# p2_half_bridge.net
KiCad netlist of a schematic drawn in Altium Designer
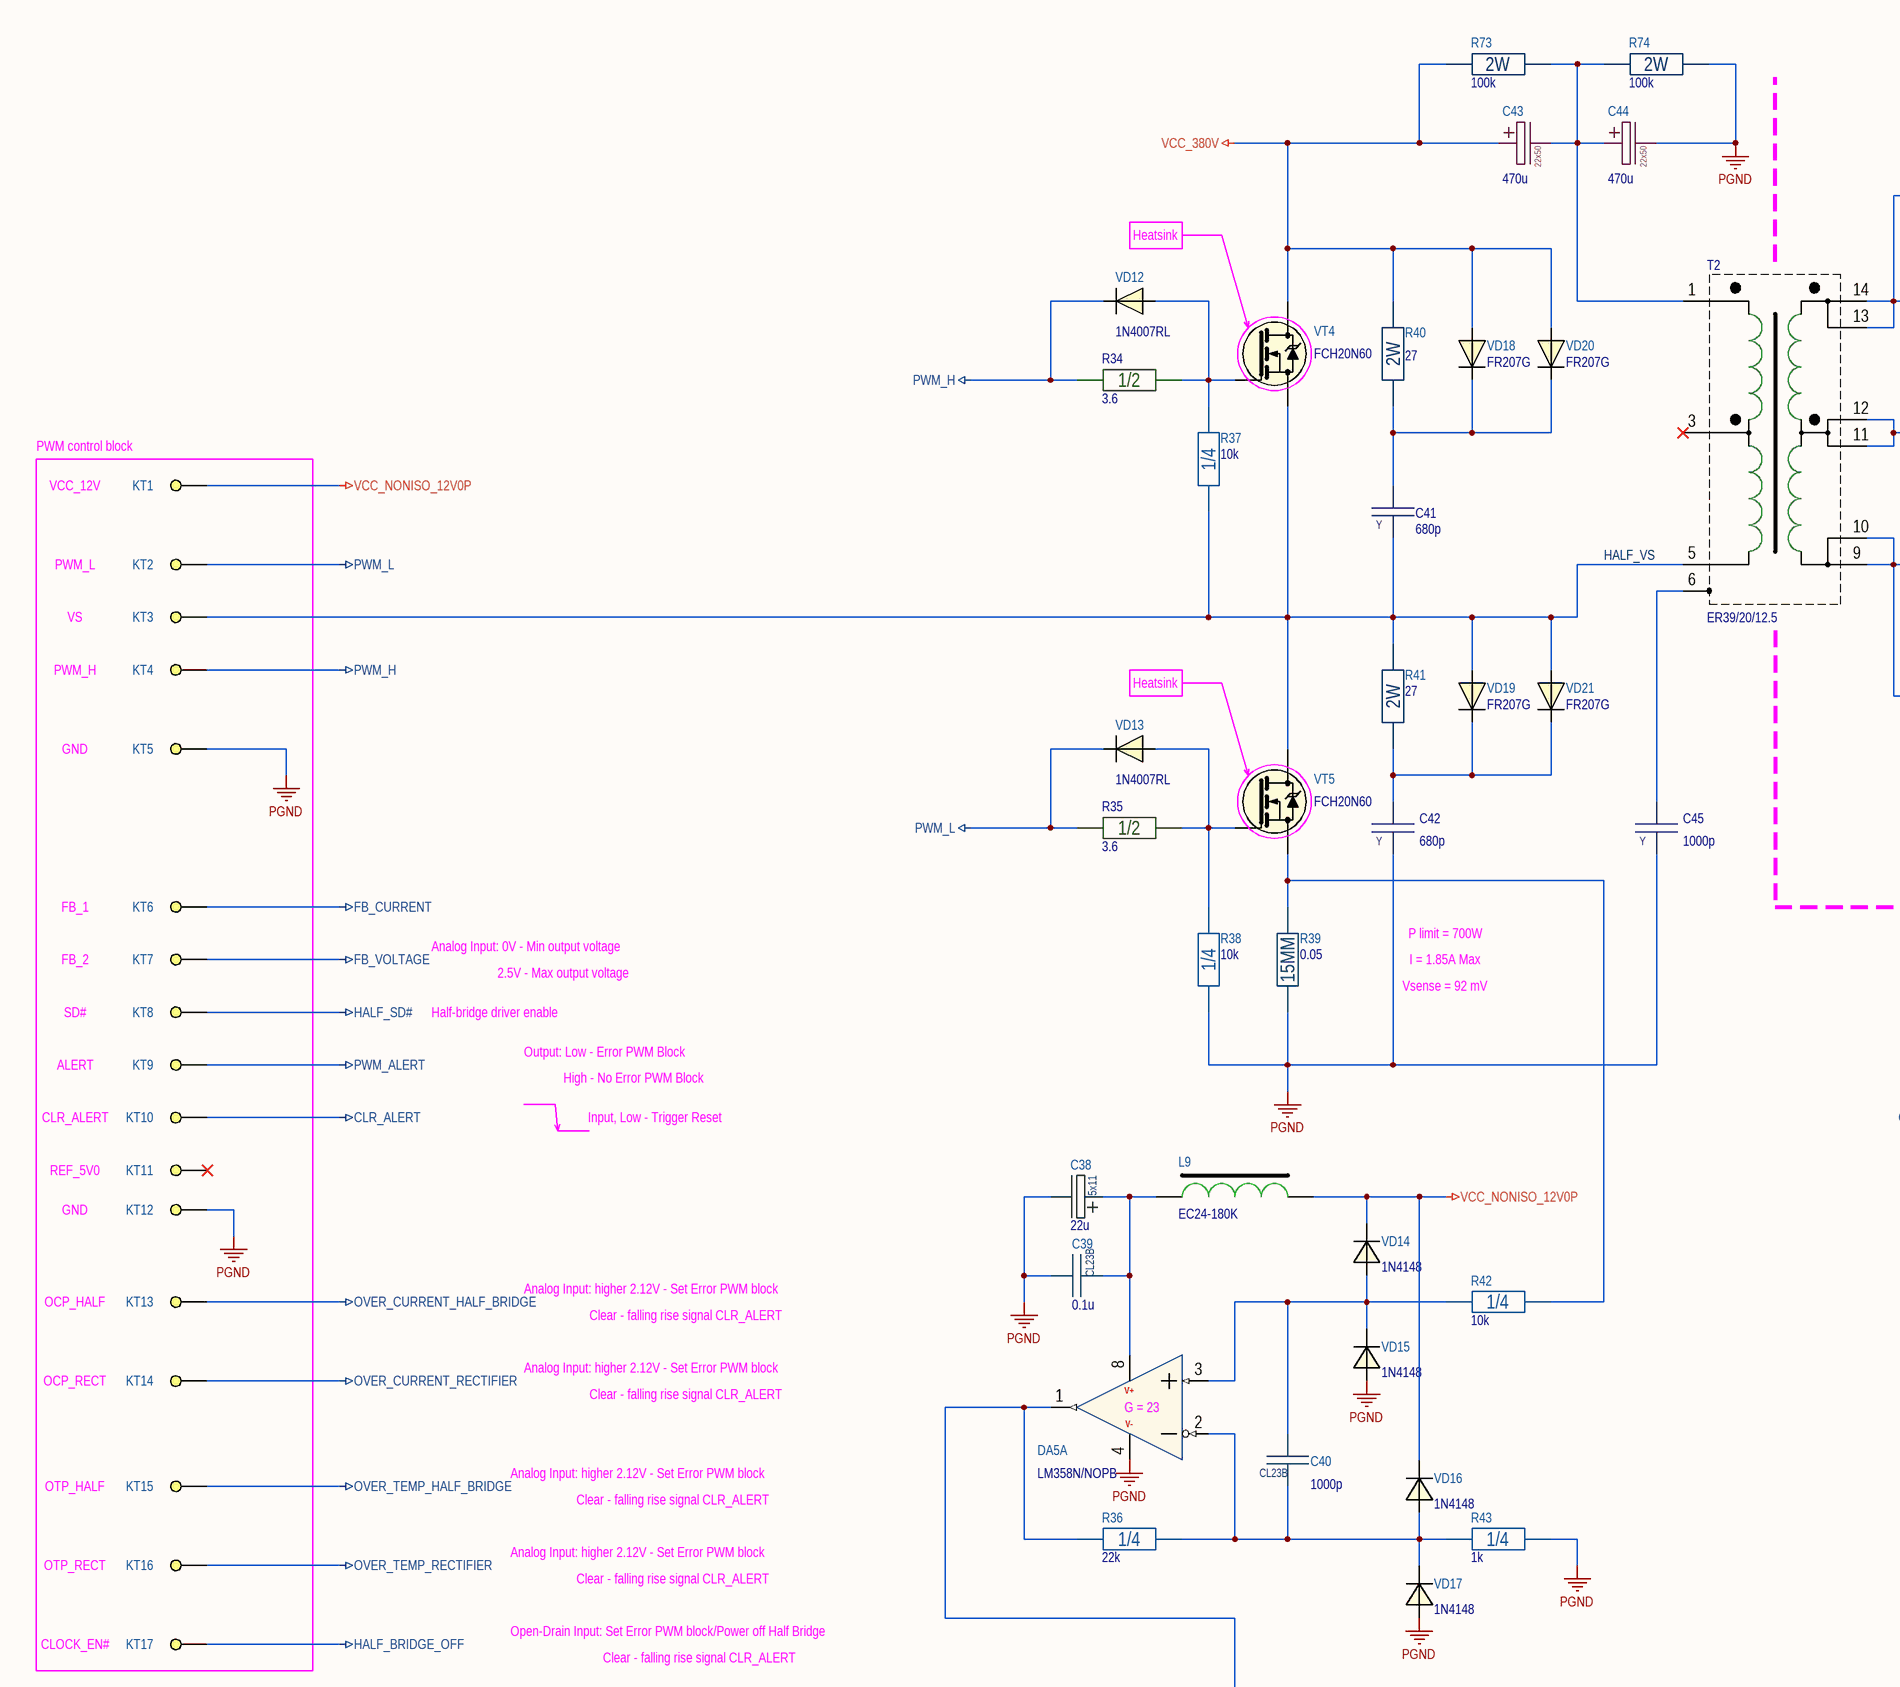
[diagram p0: p2_half_bridge.SchDoc, top left]
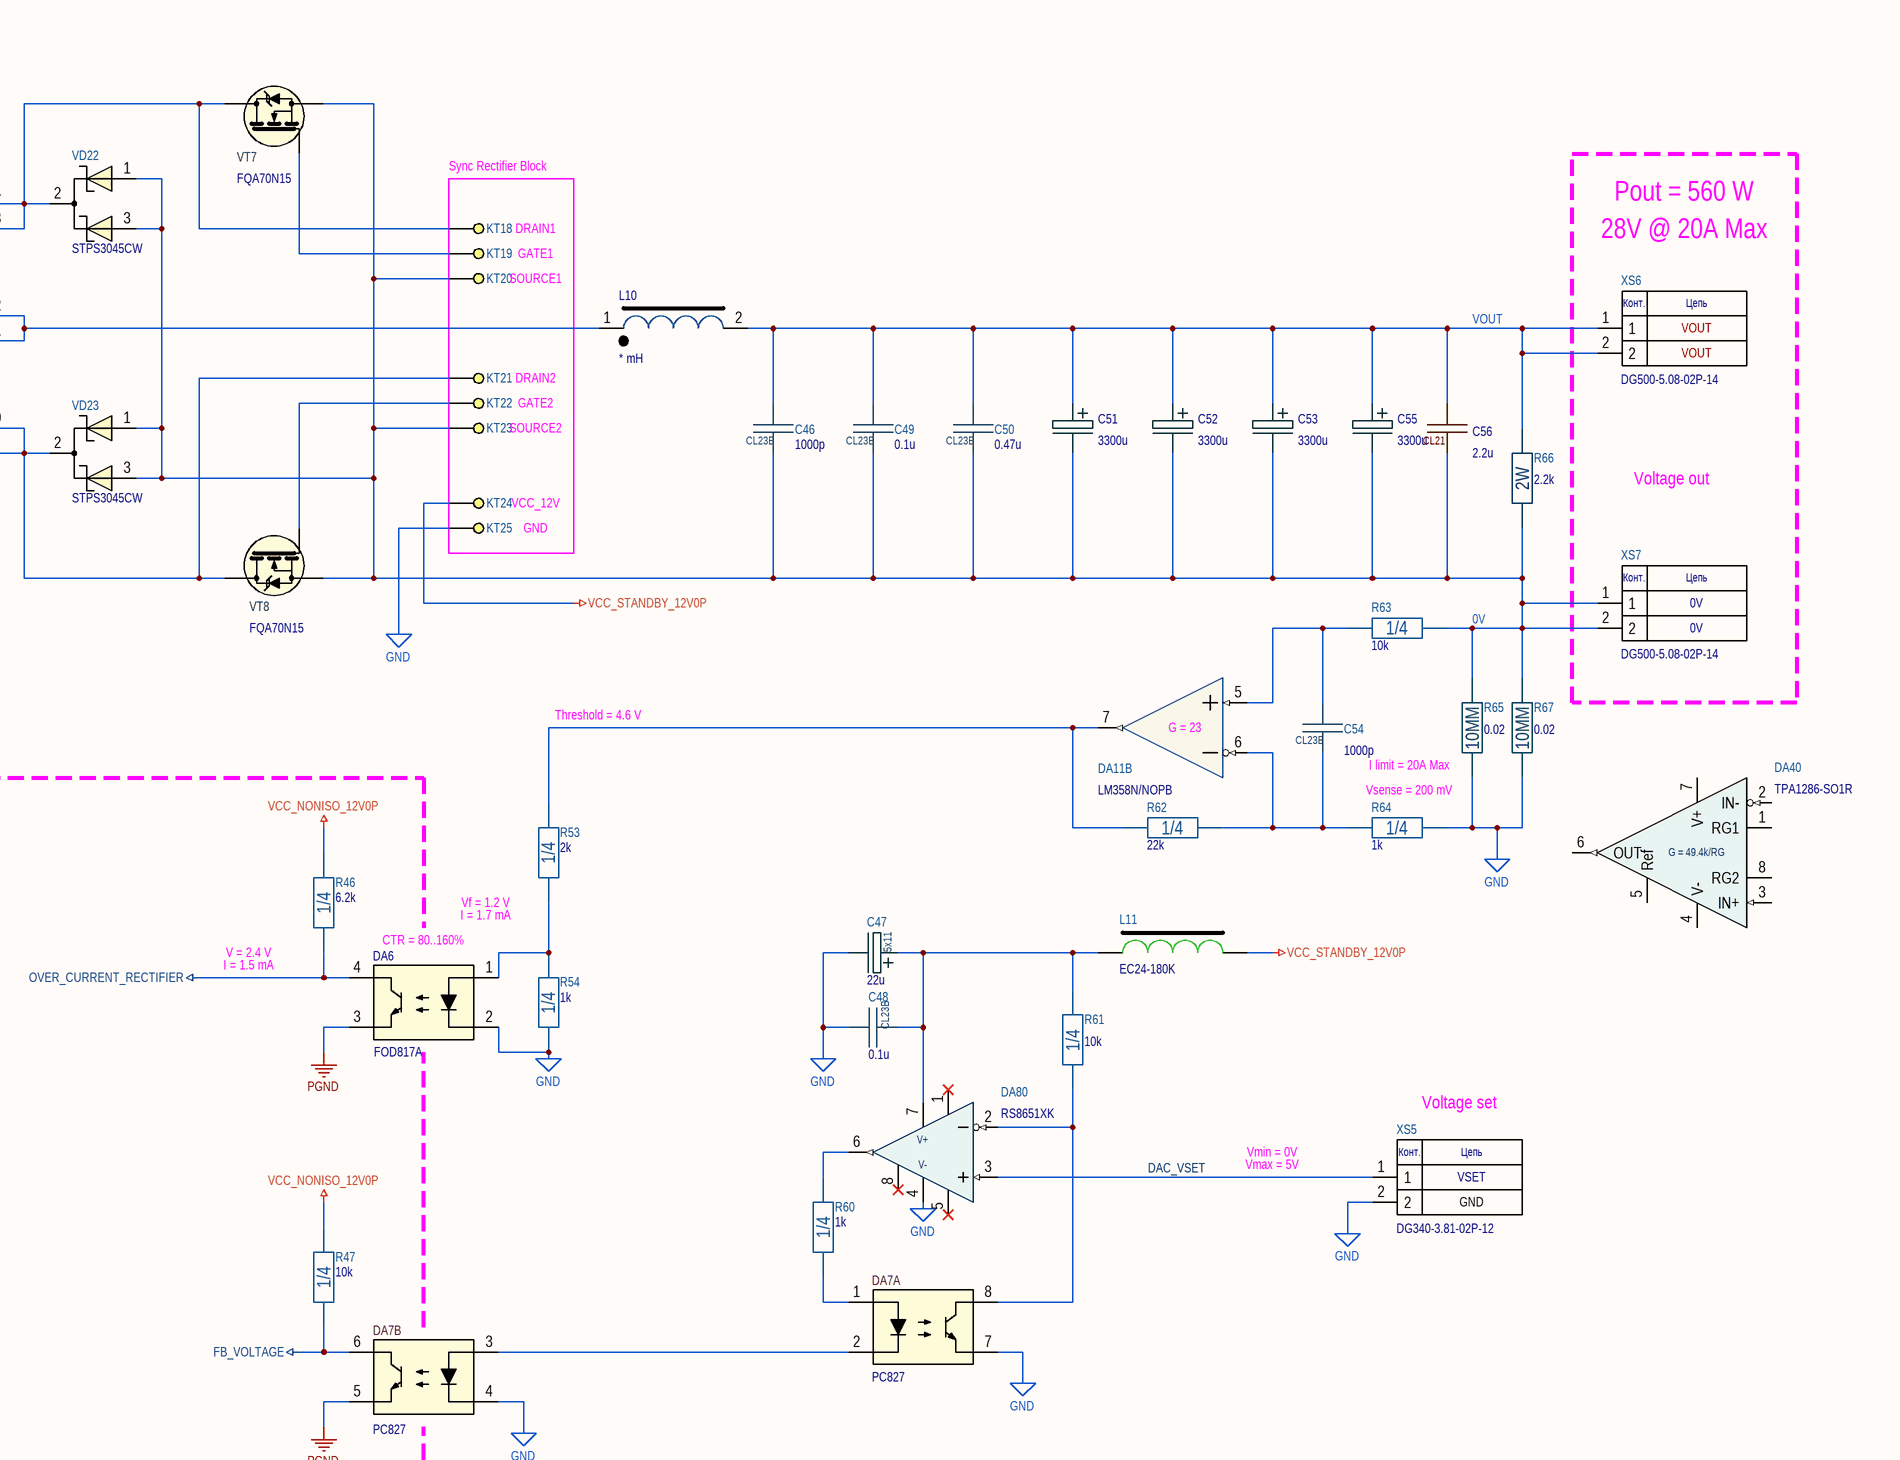
[diagram p1: p2_half_bridge.SchDoc, top right]
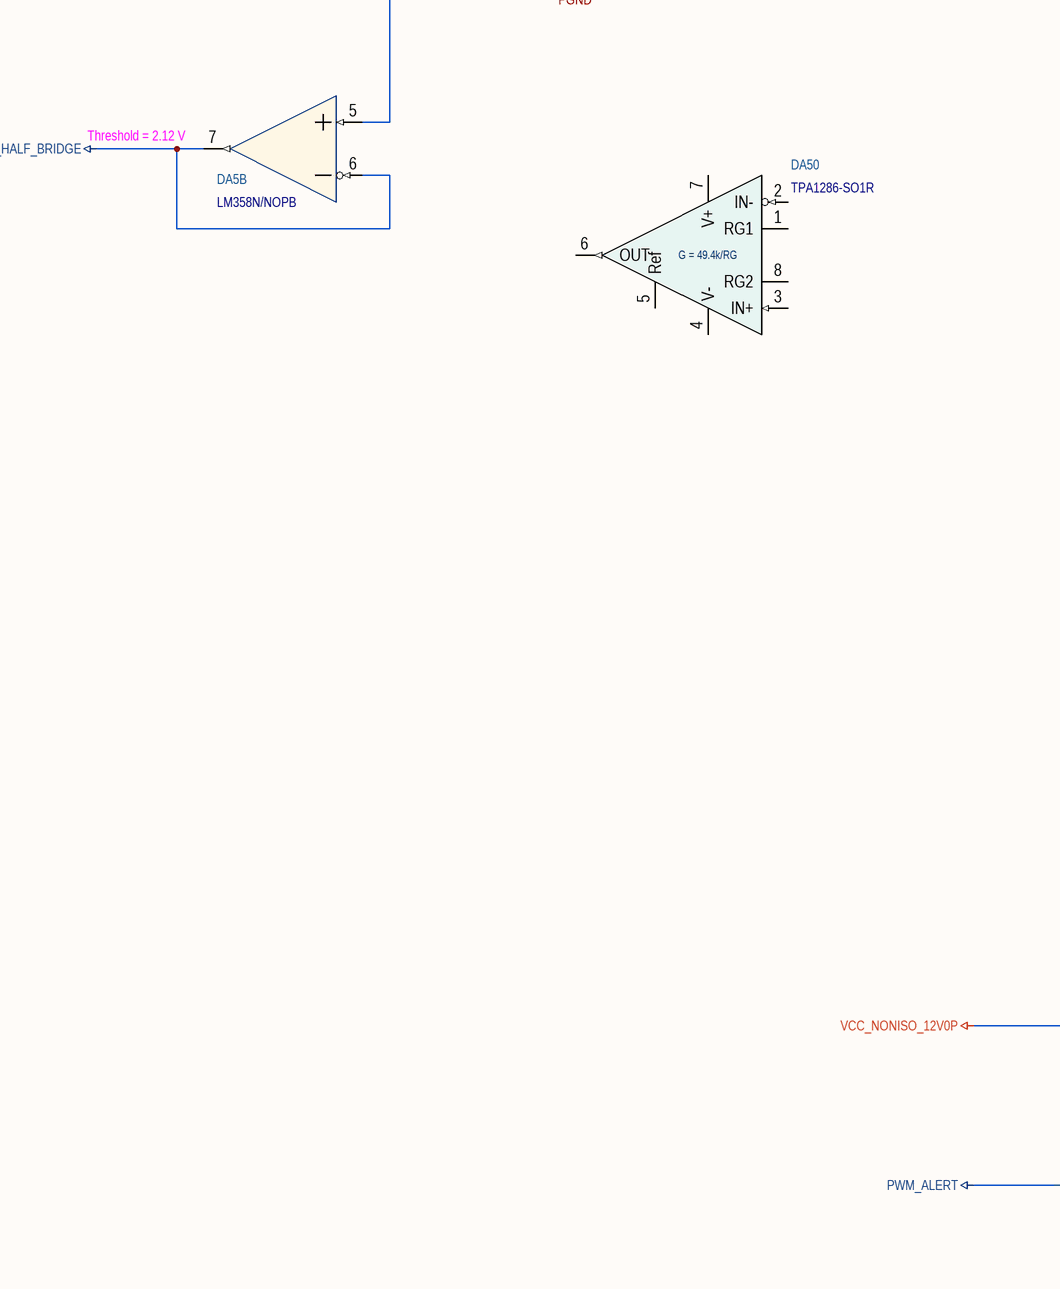
[diagram p2: p2_half_bridge.SchDoc, bottom left]
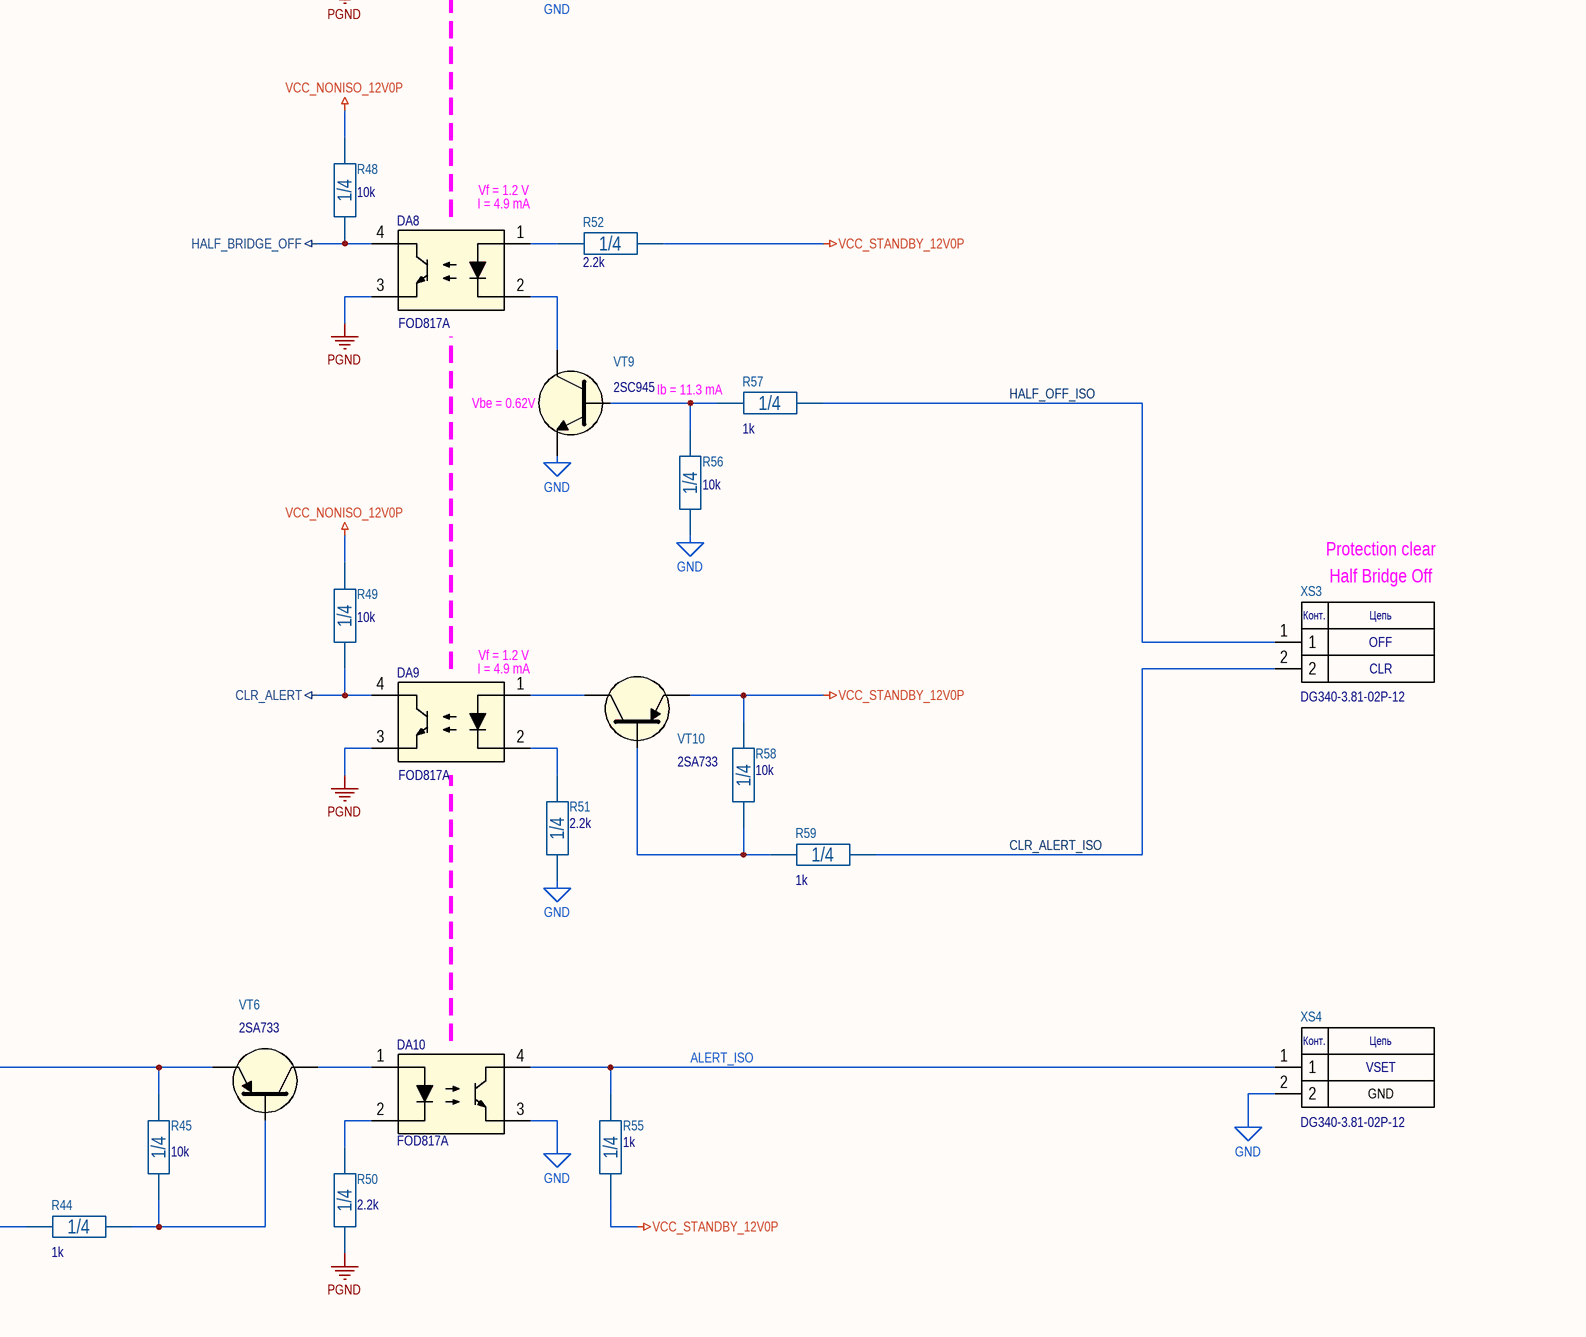
[diagram p3: p2_half_bridge.SchDoc, bottom right]

(export (version "E")
  (design (tool "Eeschema 10.0.6"))
  (components
    (comp (ref "C38")
      (value "22u")
      (footprint "PcbLib_RC:ECAP5X11X2.0_BRW")
      (description "Aluminium capacitor")
      (fields
        (field (name "TOLERANCE") "± 20 %")
        (field (name "VOLTAGE") "63V")
        (field (name "PACKAGE") "5x11")
      )
      (libsource (lib "Schlib_RC") (part "C_ECAP"))
    )
    (comp (ref "C39")
      (value "0.1u")
      (footprint "PcbLib_RC:CL23B_7.2x2.5")
      (description "Box-type metallized polyester film capacitor")
      (fields
        (field (name "TOLERANCE") "± * %")
        (field (name "VOLTAGE") "63V")
        (field (name "PACKAGE") "CL23B")
      )
      (libsource (lib "Schlib_RC") (part "CL23B"))
    )
    (comp (ref "C40")
      (value "1000p")
      (footprint "PcbLib_RC:CL23B_7.2x2.5")
      (description "Box-type metallized polyester film capacitor")
      (fields
        (field (name "TOLERANCE") "± * %")
        (field (name "VOLTAGE") "63V")
        (field (name "PACKAGE") "CL23B")
      )
      (libsource (lib "Schlib_RC") (part "CL23B"))
    )
    (comp (ref "C41")
      (value "680p")
      (footprint "PcbLib_RC:JYC_Y2_CAP_7.5")
      (description "High Voltage Ceramic Capacitor")
      (fields
        (field (name "TOLERANCE") "± 10 %")
        (field (name "VOLTAGE") "2000V")
        (field (name "PACKAGE") "Y")
      )
      (libsource (lib "Schlib_RC") (part "JB_Y2"))
    )
    (comp (ref "C42")
      (value "680p")
      (footprint "PcbLib_RC:JYC_Y2_CAP_7.5")
      (description "High Voltage Ceramic Capacitor")
      (fields
        (field (name "TOLERANCE") "± 10 %")
        (field (name "VOLTAGE") "2000V")
        (field (name "PACKAGE") "Y")
      )
      (libsource (lib "Schlib_RC") (part "JB_Y2"))
    )
    (comp (ref "C43")
      (value "470u")
      (footprint "PcbLib_RC:ECAP22X50X10")
      (description "Aluminium capacitors 35x50mm")
      (fields
        (field (name "TOLERANCE") "± 20 %")
        (field (name "VOLTAGE") "200V")
        (field (name "PACKAGE") "22x50")
      )
      (libsource (lib "Schlib_RC") (part "ECAP_22x50"))
    )
    (comp (ref "C44")
      (value "470u")
      (footprint "PcbLib_RC:ECAP22X50X10")
      (description "Aluminium capacitors 35x50mm")
      (fields
        (field (name "TOLERANCE") "± 20 %")
        (field (name "VOLTAGE") "200V")
        (field (name "PACKAGE") "22x50")
      )
      (libsource (lib "Schlib_RC") (part "ECAP_22x50"))
    )
    (comp (ref "C45")
      (value "1000p")
      (footprint "PcbLib_RC:JYC_Y2_CAP_7.5")
      (description "High Voltage Ceramic Capacitor")
      (fields
        (field (name "TOLERANCE") "± 20 %")
        (field (name "VOLTAGE") "2000V")
        (field (name "PACKAGE") "Y")
      )
      (libsource (lib "Schlib_RC") (part "JB_Y2"))
    )
    (comp (ref "C46")
      (value "1000p")
      (footprint "PcbLib_RC:CL23B_7.2x2.5")
      (description "Box-type metallized polyester film capacitor")
      (fields
        (field (name "TOLERANCE") "± * %")
        (field (name "VOLTAGE") "63V")
        (field (name "PACKAGE") "CL23B")
      )
      (libsource (lib "Schlib_RC") (part "CL23B"))
    )
    (comp (ref "C47")
      (value "22u")
      (footprint "PcbLib_RC:ECAP5X11X2.0_BRW")
      (description "Aluminium capacitor")
      (fields
        (field (name "TOLERANCE") "± 20 %")
        (field (name "VOLTAGE") "63V")
        (field (name "PACKAGE") "5x11")
      )
      (libsource (lib "Schlib_RC") (part "C_ECAP"))
    )
    (comp (ref "C48")
      (value "0.1u")
      (footprint "PcbLib_RC:CL23B_7.2x2.5")
      (description "Box-type metallized polyester film capacitor")
      (fields
        (field (name "TOLERANCE") "± * %")
        (field (name "VOLTAGE") "63V")
        (field (name "PACKAGE") "CL23B")
      )
      (libsource (lib "Schlib_RC") (part "CL23B"))
    )
    (comp (ref "C49")
      (value "0.1u")
      (footprint "PcbLib_RC:CL23B_7.2x2.5")
      (description "Box-type metallized polyester film capacitor")
      (fields
        (field (name "TOLERANCE") "± * %")
        (field (name "VOLTAGE") "63V")
        (field (name "PACKAGE") "CL23B")
      )
      (libsource (lib "Schlib_RC") (part "CL23B"))
    )
    (comp (ref "C50")
      (value "0.47u")
      (footprint "PcbLib_RC:CL23B_7.2x3.5")
      (description "Box-type metallized polyester film capacitor")
      (fields
        (field (name "TOLERANCE") "± * %")
        (field (name "VOLTAGE") "63V")
        (field (name "PACKAGE") "CL23B")
      )
      (libsource (lib "Schlib_RC") (part "CL23B"))
    )
    (comp (ref "C51")
      (value "3300u")
      (footprint "PcbLib_RC:ECAP16X36X75_BLK")
      (description "Aluminium capacitor")
      (fields (field (name "TOLERANCE") "± 20 %") (field (name "VOLTAGE") "50V"))
      (libsource (lib "Schlib_RC") (part "C_ECAP"))
    )
    (comp (ref "C52")
      (value "3300u")
      (footprint "PcbLib_RC:ECAP16X36X75_BLK")
      (description "Aluminium capacitor")
      (fields (field (name "TOLERANCE") "± 20 %") (field (name "VOLTAGE") "50V"))
      (libsource (lib "Schlib_RC") (part "C_ECAP"))
    )
    (comp (ref "C53")
      (value "3300u")
      (footprint "PcbLib_RC:ECAP16X36X75_BLK")
      (description "Aluminium capacitor")
      (fields (field (name "TOLERANCE") "± 20 %") (field (name "VOLTAGE") "50V"))
      (libsource (lib "Schlib_RC") (part "C_ECAP"))
    )
    (comp (ref "C54")
      (value "1000p")
      (footprint "PcbLib_RC:CL23B_7.2x2.5")
      (description "Box-type metallized polyester film capacitor")
      (fields
        (field (name "TOLERANCE") "± * %")
        (field (name "VOLTAGE") "63V")
        (field (name "PACKAGE") "CL23B")
      )
      (libsource (lib "Schlib_RC") (part "CL23B"))
    )
    (comp (ref "C55")
      (value "3300u")
      (footprint "PcbLib_RC:ECAP16X36X75_BLK")
      (description "Aluminium capacitor")
      (fields (field (name "TOLERANCE") "± 20 %") (field (name "VOLTAGE") "50V"))
      (libsource (lib "Schlib_RC") (part "C_ECAP"))
    )
    (comp (ref "C56")
      (value "2.2u")
      (footprint "PcbLib_RC:CL21_29x24.5x14.0_P27.5")
      (description "CL21 Type Metallized Polyester Film Capacitor")
      (fields
        (field (name "TOLERANCE") "± * %")
        (field (name "VOLTAGE") "250V")
        (field (name "PACKAGE") "CL21")
      )
      (libsource (lib "Schlib_RC") (part "CL21"))
    )
    (comp (ref "DA5")
      (value "LM358N/NOPB")
      (footprint "PcbLib_ICs:DIP-8P-M01_with_SO8")
      (description "Low-Power, Dual-Operational Amplifiers")
      (fields (field (name "MANUFACTURER") "Texas Instruments"))
      (libsource (lib "Schlib_Texas_Instruments") (part "LM358N/NOPB"))
    )
    (comp (ref "DA6")
      (value "FOD817A")
      (footprint "PcbLib_ICs:DIP-4P")
      (description "5kV Phototransistor Optocoupler")
      (fields (field (name "MANUFACTURER") "ON Semiconductor"))
      (libsource (lib "Schlib_ONSemiconductor") (part "FOD817A"))
    )
    (comp (ref "DA7")
      (value "PC827")
      (footprint "PcbLib_ICs:DIP-8P-M01")
      (description "High Density Mounting Type Photocoupler")
      (fields (field (name "MANUFACTURER") "Sharp"))
      (libsource (lib "") (part "PC827_1"))
    )
    (comp (ref "DA8")
      (value "FOD817A")
      (footprint "PcbLib_ICs:DIP-4P")
      (description "5kV Phototransistor Optocoupler")
      (fields (field (name "MANUFACTURER") "ON Semiconductor"))
      (libsource (lib "Schlib_ONSemiconductor") (part "FOD817A"))
    )
    (comp (ref "DA9")
      (value "FOD817A")
      (footprint "PcbLib_ICs:DIP-4P")
      (description "5kV Phototransistor Optocoupler")
      (fields (field (name "MANUFACTURER") "ON Semiconductor"))
      (libsource (lib "Schlib_ONSemiconductor") (part "FOD817A"))
    )
    (comp (ref "DA10")
      (value "FOD817A")
      (footprint "PcbLib_ICs:DIP-4P")
      (description "5kV Phototransistor Optocoupler")
      (fields (field (name "MANUFACTURER") "ON Semiconductor"))
      (libsource (lib "") (part "FOD817A_1"))
    )
    (comp (ref "DA11")
      (value "LM358N/NOPB")
      (footprint "PcbLib_ICs:DIP-8P-M01_with_SO8")
      (description "Low-Power, Dual-Operational Amplifiers")
      (fields (field (name "MANUFACTURER") "Texas Instruments"))
      (libsource (lib "Schlib_Texas_Instruments") (part "LM358N/NOPB"))
    )
    (comp (ref "DA40")
      (value "TPA1286-SO1R")
      (footprint "PcbLib_ICs:SOIC-8")
      (description "High Voltage, Precision, Zero-drift, Instrumentation Amplifier")
      (fields (field (name "MANUFACTURER") "3PEAK"))
      (libsource (lib "Schlib_3Peak") (part "TPA1286-SO1R"))
    )
    (comp (ref "DA50")
      (value "TPA1286-SO1R")
      (footprint "PcbLib_ICs:SOIC-8")
      (description "High Voltage, Precision, Zero-drift, Instrumentation Amplifier")
      (fields (field (name "MANUFACTURER") "3PEAK"))
      (libsource (lib "Schlib_3Peak") (part "TPA1286-SO1R"))
    )
    (comp (ref "DA80")
      (value "RS8651XK")
      (footprint "PcbLib_ICs:SOIC-8")
      (description "Precision, Zero-Drift, Rail-to-Rail Out, High-Voltage(32V) Operational Amplifier")
      (fields (field (name "MANUFACTURER") "Jiangsu Runic Technology"))
      (libsource (lib "Schlib_Runic") (part "RS8651XK"))
    )
    (comp (ref "KT1")
      (value "TEST_PAD")
      (footprint "PcbLib_Others:TEST_PAD_HOLE1.1x1.8SQ")
      (description "Test pad")
      (libsource (lib "Schlib_OtherComponents") (part "TEST_PAD"))
    )
    (comp (ref "KT2")
      (value "TEST_PAD")
      (footprint "PcbLib_Others:TEST_PAD_HOLE1.1x1.8")
      (description "Test pad")
      (libsource (lib "Schlib_OtherComponents") (part "TEST_PAD"))
    )
    (comp (ref "KT3")
      (value "TEST_PAD")
      (footprint "PcbLib_Others:TEST_PAD_HOLE1.1x1.8")
      (description "Test pad")
      (libsource (lib "Schlib_OtherComponents") (part "TEST_PAD"))
    )
    (comp (ref "KT4")
      (value "TEST_PAD")
      (footprint "PcbLib_Others:TEST_PAD_HOLE1.1x1.8")
      (description "Test pad")
      (libsource (lib "Schlib_OtherComponents") (part "TEST_PAD"))
    )
    (comp (ref "KT5")
      (value "TEST_PAD")
      (footprint "PcbLib_Others:TEST_PAD_HOLE1.1x1.8")
      (description "Test pad")
      (libsource (lib "Schlib_OtherComponents") (part "TEST_PAD"))
    )
    (comp (ref "KT6")
      (value "TEST_PAD")
      (footprint "PcbLib_Others:TEST_PAD_HOLE1.1x1.8")
      (description "Test pad")
      (libsource (lib "Schlib_OtherComponents") (part "TEST_PAD"))
    )
    (comp (ref "KT7")
      (value "TEST_PAD")
      (footprint "PcbLib_Others:TEST_PAD_HOLE1.1x1.8")
      (description "Test pad")
      (libsource (lib "Schlib_OtherComponents") (part "TEST_PAD"))
    )
    (comp (ref "KT8")
      (value "TEST_PAD")
      (footprint "PcbLib_Others:TEST_PAD_HOLE1.1x1.8")
      (description "Test pad")
      (libsource (lib "Schlib_OtherComponents") (part "TEST_PAD"))
    )
    (comp (ref "KT9")
      (value "TEST_PAD")
      (footprint "PcbLib_Others:TEST_PAD_HOLE1.1x1.8")
      (description "Test pad")
      (libsource (lib "Schlib_OtherComponents") (part "TEST_PAD"))
    )
    (comp (ref "KT10")
      (value "TEST_PAD")
      (footprint "PcbLib_Others:TEST_PAD_HOLE1.1x1.8")
      (description "Test pad")
      (libsource (lib "Schlib_OtherComponents") (part "TEST_PAD"))
    )
    (comp (ref "KT11")
      (value "TEST_PAD")
      (footprint "PcbLib_Others:TEST_PAD_HOLE1.1x1.8")
      (description "Test pad")
      (libsource (lib "Schlib_OtherComponents") (part "TEST_PAD"))
    )
    (comp (ref "KT12")
      (value "TEST_PAD")
      (footprint "PcbLib_Others:TEST_PAD_HOLE1.1x1.8")
      (description "Test pad")
      (libsource (lib "Schlib_OtherComponents") (part "TEST_PAD"))
    )
    (comp (ref "KT13")
      (value "TEST_PAD")
      (footprint "PcbLib_Others:TEST_PAD_HOLE1.1x1.8")
      (description "Test pad")
      (libsource (lib "Schlib_OtherComponents") (part "TEST_PAD"))
    )
    (comp (ref "KT14")
      (value "TEST_PAD")
      (footprint "PcbLib_Others:TEST_PAD_HOLE1.1x1.8")
      (description "Test pad")
      (libsource (lib "Schlib_OtherComponents") (part "TEST_PAD"))
    )
    (comp (ref "KT15")
      (value "TEST_PAD")
      (footprint "PcbLib_Others:TEST_PAD_HOLE1.1x1.8")
      (description "Test pad")
      (libsource (lib "Schlib_OtherComponents") (part "TEST_PAD"))
    )
    (comp (ref "KT16")
      (value "TEST_PAD")
      (footprint "PcbLib_Others:TEST_PAD_HOLE1.1x1.8")
      (description "Test pad")
      (libsource (lib "Schlib_OtherComponents") (part "TEST_PAD"))
    )
    (comp (ref "KT17")
      (value "TEST_PAD")
      (footprint "PcbLib_Others:TEST_PAD_HOLE1.1x1.8")
      (description "Test pad")
      (libsource (lib "Schlib_OtherComponents") (part "TEST_PAD"))
    )
    (comp (ref "KT18")
      (value "TEST_PAD")
      (footprint "PcbLib_Others:TEST_PAD_HOLE1.1x1.8")
      (description "Test pad")
      (libsource (lib "Schlib_OtherComponents") (part "TEST_PAD"))
    )
    (comp (ref "KT19")
      (value "TEST_PAD")
      (footprint "PcbLib_Others:TEST_PAD_HOLE1.1x1.8")
      (description "Test pad")
      (libsource (lib "Schlib_OtherComponents") (part "TEST_PAD"))
    )
    (comp (ref "KT20")
      (value "TEST_PAD")
      (footprint "PcbLib_Others:TEST_PAD_HOLE1.1x1.8")
      (description "Test pad")
      (libsource (lib "Schlib_OtherComponents") (part "TEST_PAD"))
    )
    (comp (ref "KT21")
      (value "TEST_PAD")
      (footprint "PcbLib_Others:TEST_PAD_HOLE1.1x1.8")
      (description "Test pad")
      (libsource (lib "Schlib_OtherComponents") (part "TEST_PAD"))
    )
    (comp (ref "KT22")
      (value "TEST_PAD")
      (footprint "PcbLib_Others:TEST_PAD_HOLE1.1x1.8")
      (description "Test pad")
      (libsource (lib "Schlib_OtherComponents") (part "TEST_PAD"))
    )
    (comp (ref "KT23")
      (value "TEST_PAD")
      (footprint "PcbLib_Others:TEST_PAD_HOLE1.1x1.8")
      (description "Test pad")
      (libsource (lib "Schlib_OtherComponents") (part "TEST_PAD"))
    )
    (comp (ref "KT24")
      (value "TEST_PAD")
      (footprint "PcbLib_Others:TEST_PAD_HOLE1.1x1.8")
      (description "Test pad")
      (libsource (lib "Schlib_OtherComponents") (part "TEST_PAD"))
    )
    (comp (ref "KT25")
      (value "TEST_PAD")
      (footprint "PcbLib_Others:TEST_PAD_HOLE1.1x1.8")
      (description "Test pad")
      (libsource (lib "Schlib_OtherComponents") (part "TEST_PAD"))
    )
    (comp (ref "L9")
      (value "EC24-180K")
      (footprint "PcbLib_RC:EC24_GREEN_VERT")
      (description "Axial leaded coated inductors")
      (fields (field (name "MANUFACTURER") "3L Electronic"))
      (libsource (lib "Schlib_RC") (part "EC24"))
    )
    (comp (ref "L10")
      (value "* mH")
      (footprint "PcbLib_RC:CORE_D33_GB")
      (description "Ferrite Core D32.8/20.1/10.7 mm")
      (libsource (lib "Schlib_OtherComponents") (part "CORE_D33"))
    )
    (comp (ref "L11")
      (value "EC24-180K")
      (footprint "PcbLib_RC:EC24_GREEN")
      (description "Axial leaded coated inductors")
      (fields (field (name "MANUFACTURER") "3L Electronic"))
      (libsource (lib "Schlib_RC") (part "EC24"))
    )
    (comp (ref "R34")
      (value "3.6")
      (footprint "PcbLib_RC:CFR-50(VERTICAL)")
      (description "Resistor 1/2W")
      (fields
        (field (name "TOLERANCE") "± 5 %")
        (field (name "PART NUMBER") "MFR-50JT-52-3R6")
        (field (name "PACKAGE") "1/2")
      )
      (libsource (lib "Schlib_RC") (part "CF50"))
    )
    (comp (ref "R35")
      (value "3.6")
      (footprint "PcbLib_RC:CFR-50(VERTICAL)")
      (description "Resistor 1/2W")
      (fields
        (field (name "TOLERANCE") "± 5 %")
        (field (name "PART NUMBER") "MFR-50JT-52-3R6")
        (field (name "PACKAGE") "1/2")
      )
      (libsource (lib "Schlib_RC") (part "CF50"))
    )
    (comp (ref "R36")
      (value "22k")
      (footprint "PcbLib_RC:CFR-25(VERTICAL)")
      (description "Resistor 1/4W")
      (fields
        (field (name "TOLERANCE") "± 1 %")
        (field (name "PART NUMBER") "MFR-25FTF52-22K")
        (field (name "PACKAGE") "1/4")
      )
      (libsource (lib "Schlib_RC") (part "CF25"))
    )
    (comp (ref "R37")
      (value "10k")
      (footprint "PcbLib_RC:CFR-25")
      (description "Resistor 1/4W")
      (fields
        (field (name "TOLERANCE") "± 1 %")
        (field (name "PART NUMBER") "MFR-25FTF52-10K")
        (field (name "PACKAGE") "1/4")
      )
      (libsource (lib "Schlib_RC") (part "CF25"))
    )
    (comp (ref "R38")
      (value "10k")
      (footprint "PcbLib_RC:CFR-25")
      (description "Resistor 1/4W")
      (fields
        (field (name "TOLERANCE") "± 1 %")
        (field (name "PART NUMBER") "MFR-25FTF52-10K")
        (field (name "PACKAGE") "1/4")
      )
      (libsource (lib "Schlib_RC") (part "CF25"))
    )
    (comp (ref "R39")
      (value "0.05")
      (footprint "PcbLib_RC:CURRENT_SENSE_15x18mm")
      (description "Constantan shunt resistor, pitch = 15mm")
      (fields (field (name "TOLERANCE") "±  %") (field (name "PACKAGE") "15MM"))
      (libsource (lib "Schlib_RC") (part "SHUNT_15MM"))
    )
    (comp (ref "R40")
      (value "27")
      (footprint "PcbLib_RC:CFR-200(VERTICAL)")
      (description "Resistor 2W")
      (fields
        (field (name "TOLERANCE") "± 5 %")
        (field (name "PART NUMBER") "KNP200JB-73-27R")
        (field (name "PACKAGE") "2W")
      )
      (libsource (lib "Schlib_RC") (part "CF200"))
    )
    (comp (ref "R41")
      (value "27")
      (footprint "PcbLib_RC:CFR-200(VERTICAL)")
      (description "Resistor 2W")
      (fields
        (field (name "TOLERANCE") "± 5 %")
        (field (name "PART NUMBER") "KNP200JB-73-27R")
        (field (name "PACKAGE") "2W")
      )
      (libsource (lib "Schlib_RC") (part "CF200"))
    )
    (comp (ref "R42")
      (value "10k")
      (footprint "PcbLib_RC:CFR-25(VERTICAL)")
      (description "Resistor 1/4W")
      (fields
        (field (name "TOLERANCE") "± 1 %")
        (field (name "PART NUMBER") "MFR-25FTF52-10K")
        (field (name "PACKAGE") "1/4")
      )
      (libsource (lib "Schlib_RC") (part "CF25"))
    )
    (comp (ref "R43")
      (value "1k")
      (footprint "PcbLib_RC:CFR-25(VERTICAL)")
      (description "Resistor 1/4W")
      (fields
        (field (name "TOLERANCE") "± 1 %")
        (field (name "PART NUMBER") "MFR-25FTF52-1K")
        (field (name "PACKAGE") "1/4")
      )
      (libsource (lib "Schlib_RC") (part "CF25"))
    )
    (comp (ref "R44")
      (value "1k")
      (footprint "PcbLib_RC:CFR-25(VERTICAL)")
      (description "Resistor 1/4W")
      (fields
        (field (name "TOLERANCE") "± 1 %")
        (field (name "PART NUMBER") "MFR-25FTF52-1K")
        (field (name "PACKAGE") "1/4")
      )
      (libsource (lib "Schlib_RC") (part "CF25"))
    )
    (comp (ref "R45")
      (value "10k")
      (footprint "PcbLib_RC:CFR-25(VERTICAL)")
      (description "Resistor 1/4W")
      (fields
        (field (name "TOLERANCE") "± 1 %")
        (field (name "PART NUMBER") "MFR-25FTF52-10K")
        (field (name "PACKAGE") "1/4")
      )
      (libsource (lib "Schlib_RC") (part "CF25"))
    )
    (comp (ref "R46")
      (value "6.2k")
      (footprint "PcbLib_RC:CFR-25(VERTICAL)")
      (description "Resistor 1/4W")
      (fields
        (field (name "TOLERANCE") "± 1 %")
        (field (name "PART NUMBER") "MFR-25FTF52-5.1K")
        (field (name "PACKAGE") "1/4")
      )
      (libsource (lib "Schlib_RC") (part "CF25"))
    )
    (comp (ref "R47")
      (value "10k")
      (footprint "PcbLib_RC:CFR-25(VERTICAL)")
      (description "Resistor 1/4W")
      (fields
        (field (name "TOLERANCE") "± 1 %")
        (field (name "PART NUMBER") "MFR-25FTF52-10K")
        (field (name "PACKAGE") "1/4")
      )
      (libsource (lib "Schlib_RC") (part "CF25"))
    )
    (comp (ref "R48")
      (value "10k")
      (footprint "PcbLib_RC:CFR-25(VERTICAL)")
      (description "Resistor 1/4W")
      (fields
        (field (name "TOLERANCE") "± 1 %")
        (field (name "PART NUMBER") "MFR-25FTF52-10K")
        (field (name "PACKAGE") "1/4")
      )
      (libsource (lib "Schlib_RC") (part "CF25"))
    )
    (comp (ref "R49")
      (value "10k")
      (footprint "PcbLib_RC:CFR-25(VERTICAL)")
      (description "Resistor 1/4W")
      (fields
        (field (name "TOLERANCE") "± 1 %")
        (field (name "PART NUMBER") "MFR-25FTF52-10K")
        (field (name "PACKAGE") "1/4")
      )
      (libsource (lib "Schlib_RC") (part "CF25"))
    )
    (comp (ref "R50")
      (value "2.2k")
      (footprint "PcbLib_RC:CFR-25(VERTICAL)")
      (description "Resistor 1/4W")
      (fields
        (field (name "TOLERANCE") "± 1 %")
        (field (name "PART NUMBER") "MFR-25FTF52-2K2")
        (field (name "PACKAGE") "1/4")
      )
      (libsource (lib "Schlib_RC") (part "CF25"))
    )
    (comp (ref "R51")
      (value "2.2k")
      (footprint "PcbLib_RC:CFR-25(VERTICAL)")
      (description "Resistor 1/4W")
      (fields
        (field (name "TOLERANCE") "± 1 %")
        (field (name "PART NUMBER") "MFR-25FTF52-2K2")
        (field (name "PACKAGE") "1/4")
      )
      (libsource (lib "Schlib_RC") (part "CF25"))
    )
    (comp (ref "R52")
      (value "2.2k")
      (footprint "PcbLib_RC:CFR-25(VERTICAL)")
      (description "Resistor 1/4W")
      (fields
        (field (name "TOLERANCE") "± 1 %")
        (field (name "PART NUMBER") "MFR-25FTF52-2K2")
        (field (name "PACKAGE") "1/4")
      )
      (libsource (lib "Schlib_RC") (part "CF25"))
    )
    (comp (ref "R53")
      (value "2k")
      (footprint "PcbLib_RC:CFR-25(VERTICAL)")
      (description "Resistor 1/4W")
      (fields
        (field (name "TOLERANCE") "± 1 %")
        (field (name "PART NUMBER") "MFR-25FTF52-2K")
        (field (name "PACKAGE") "1/4")
      )
      (libsource (lib "Schlib_RC") (part "CF25"))
    )
    (comp (ref "R54")
      (value "1k")
      (footprint "PcbLib_RC:CFR-25(VERTICAL)")
      (description "Resistor 1/4W")
      (fields
        (field (name "TOLERANCE") "± 1 %")
        (field (name "PART NUMBER") "MFR-25FTF52-1K")
        (field (name "PACKAGE") "1/4")
      )
      (libsource (lib "Schlib_RC") (part "CF25"))
    )
    (comp (ref "R55")
      (value "1k")
      (footprint "PcbLib_RC:CFR-25(VERTICAL)")
      (description "Resistor 1/4W")
      (fields
        (field (name "TOLERANCE") "± 1 %")
        (field (name "PART NUMBER") "MFR-25FTF52-1K")
        (field (name "PACKAGE") "1/4")
      )
      (libsource (lib "Schlib_RC") (part "CF25"))
    )
    (comp (ref "R56")
      (value "10k")
      (footprint "PcbLib_RC:CFR-25(VERTICAL)")
      (description "Resistor 1/4W")
      (fields
        (field (name "TOLERANCE") "± 1 %")
        (field (name "PART NUMBER") "MFR-25FTF52-10K")
        (field (name "PACKAGE") "1/4")
      )
      (libsource (lib "Schlib_RC") (part "CF25"))
    )
    (comp (ref "R57")
      (value "1k")
      (footprint "PcbLib_RC:CFR-25(VERTICAL)")
      (description "Resistor 1/4W")
      (fields
        (field (name "TOLERANCE") "± 1 %")
        (field (name "PART NUMBER") "MFR-25FTF52-1K")
        (field (name "PACKAGE") "1/4")
      )
      (libsource (lib "Schlib_RC") (part "CF25"))
    )
    (comp (ref "R58")
      (value "10k")
      (footprint "PcbLib_RC:CFR-25(VERTICAL)")
      (description "Resistor 1/4W")
      (fields
        (field (name "TOLERANCE") "± 1 %")
        (field (name "PART NUMBER") "MFR-25FTF52-10K")
        (field (name "PACKAGE") "1/4")
      )
      (libsource (lib "Schlib_RC") (part "CF25"))
    )
    (comp (ref "R59")
      (value "1k")
      (footprint "PcbLib_RC:CFR-25(VERTICAL)")
      (description "Resistor 1/4W")
      (fields
        (field (name "TOLERANCE") "± 1 %")
        (field (name "PART NUMBER") "MFR-25FTF52-1K")
        (field (name "PACKAGE") "1/4")
      )
      (libsource (lib "Schlib_RC") (part "CF25"))
    )
    (comp (ref "R60")
      (value "1k")
      (footprint "PcbLib_RC:CFR-25(VERTICAL)")
      (description "Resistor 1/4W")
      (fields
        (field (name "TOLERANCE") "± 1 %")
        (field (name "PART NUMBER") "MFR-25FTF52-1K")
        (field (name "PACKAGE") "1/4")
      )
      (libsource (lib "Schlib_RC") (part "CF25"))
    )
    (comp (ref "R61")
      (value "10k")
      (footprint "PcbLib_RC:CFR-25")
      (description "Resistor 1/4W")
      (fields
        (field (name "TOLERANCE") "± 1 %")
        (field (name "PART NUMBER") "MFR-25FTF52-10K")
        (field (name "PACKAGE") "1/4")
      )
      (libsource (lib "Schlib_RC") (part "CF25"))
    )
    (comp (ref "R62")
      (value "22k")
      (footprint "PcbLib_RC:CFR-25")
      (description "Resistor 1/4W")
      (fields
        (field (name "TOLERANCE") "± 1 %")
        (field (name "PART NUMBER") "MFR-25FTF52-22K")
        (field (name "PACKAGE") "1/4")
      )
      (libsource (lib "Schlib_RC") (part "CF25"))
    )
    (comp (ref "R63")
      (value "10k")
      (footprint "PcbLib_RC:CFR-25(VERTICAL)")
      (description "Resistor 1/4W")
      (fields
        (field (name "TOLERANCE") "± 1 %")
        (field (name "PART NUMBER") "MFR-25FTF52-10K")
        (field (name "PACKAGE") "1/4")
      )
      (libsource (lib "Schlib_RC") (part "CF25"))
    )
    (comp (ref "R64")
      (value "1k")
      (footprint "PcbLib_RC:CFR-25(VERTICAL)")
      (description "Resistor 1/4W")
      (fields
        (field (name "TOLERANCE") "± 1 %")
        (field (name "PART NUMBER") "MFR-25FTF52-1K")
        (field (name "PACKAGE") "1/4")
      )
      (libsource (lib "Schlib_RC") (part "CF25"))
    )
    (comp (ref "R65")
      (value "0.02")
      (footprint "PcbLib_RC:CURRENT_SENSE_10x11mm")
      (description "Constantan shunt resistor, pitch = 10mm")
      (fields (field (name "TOLERANCE") "± 5 %") (field (name "PACKAGE") "10MM"))
      (libsource (lib "Schlib_RC") (part "SHUNT_10MM"))
    )
    (comp (ref "R66")
      (value "2.2k")
      (footprint "PcbLib_RC:CFR-200(VERTICAL)")
      (description "Resistor 2W")
      (fields
        (field (name "TOLERANCE") "± 5 %")
        (field (name "PART NUMBER") "KNP200JB-73-2K2")
        (field (name "PACKAGE") "2W")
      )
      (libsource (lib "Schlib_RC") (part "CF200"))
    )
    (comp (ref "R67")
      (value "0.02")
      (footprint "PcbLib_RC:CURRENT_SENSE_10x11mm")
      (description "Constantan shunt resistor, pitch = 10mm")
      (fields (field (name "TOLERANCE") "± 5 %") (field (name "PACKAGE") "10MM"))
      (libsource (lib "Schlib_RC") (part "SHUNT_10MM"))
    )
    (comp (ref "R73")
      (value "100k")
      (footprint "PcbLib_RC:CFR-200(VERTICAL)")
      (description "Resistor 2W")
      (fields
        (field (name "TOLERANCE") "± 5 %")
        (field (name "PART NUMBER") "MFR200JT-73-100K")
        (field (name "PACKAGE") "2W")
      )
      (libsource (lib "Schlib_RC") (part "CF200"))
    )
    (comp (ref "R74")
      (value "100k")
      (footprint "PcbLib_RC:CFR-200(VERTICAL)")
      (description "Resistor 2W")
      (fields
        (field (name "TOLERANCE") "± 5 %")
        (field (name "PART NUMBER") "MFR200JT-73-100K")
        (field (name "PACKAGE") "2W")
      )
      (libsource (lib "Schlib_RC") (part "CF200"))
    )
    (comp (ref "T2")
      (value "ER39/20/12.5")
      (footprint "PcbLib_Others:ER39/20/12.5")
      (description "EE39 Ferrite Core, with footprint for ER35, EE33, EI33 etc.")
      (libsource (lib "Schlib_OtherComponents") (part "ER39"))
    )
    (comp (ref "VD12")
      (value "1N4007RL")
      (footprint "PcbLib_Discrete:DO-41")
      (description "1A 1000V Standard Recovery Rectifiers Diode")
      (fields (field (name "MANUFACTURER") "ON Semiconductor"))
      (libsource (lib "Schlib_ONSemiconductor") (part "1N4007RL"))
    )
    (comp (ref "VD13")
      (value "1N4007RL")
      (footprint "PcbLib_Discrete:DO-41")
      (description "1A 1000V Standard Recovery Rectifiers Diode")
      (fields (field (name "MANUFACTURER") "ON Semiconductor"))
      (libsource (lib "Schlib_ONSemiconductor") (part "1N4007RL"))
    )
    (comp (ref "VD14")
      (value "1N4148")
      (footprint "PcbLib_Discrete:DO-35 GLASS LIGHT RED")
      (description "High-speed diode")
      (libsource (lib "Schlib_NXP_Semiconductors") (part "1N4148"))
    )
    (comp (ref "VD15")
      (value "1N4148")
      (footprint "PcbLib_Discrete:DO-35 GLASS LIGHT RED")
      (description "High-speed diode")
      (libsource (lib "Schlib_NXP_Semiconductors") (part "1N4148"))
    )
    (comp (ref "VD16")
      (value "1N4148")
      (footprint "PcbLib_Discrete:DO-35 GLASS LIGHT RED")
      (description "High-speed diode")
      (libsource (lib "Schlib_NXP_Semiconductors") (part "1N4148"))
    )
    (comp (ref "VD17")
      (value "1N4148")
      (footprint "PcbLib_Discrete:DO-35 GLASS LIGHT RED")
      (description "High-speed diode")
      (libsource (lib "Schlib_NXP_Semiconductors") (part "1N4148"))
    )
    (comp (ref "VD18")
      (value "FR207G")
      (footprint "PcbLib_Discrete:DO-15")
      (description "Diode 2A, 1000V Glass Passivated Fast Recovery Rectifiers")
      (fields (field (name "MANUFACTURER") "Taiwan Semiconductor Corporation"))
      (libsource (lib "Schlib_Taiwan_Semiconductor") (part "FR207G"))
    )
    (comp (ref "VD19")
      (value "FR207G")
      (footprint "PcbLib_Discrete:DO-15")
      (description "Diode 2A, 1000V Glass Passivated Fast Recovery Rectifiers")
      (fields (field (name "MANUFACTURER") "Taiwan Semiconductor Corporation"))
      (libsource (lib "Schlib_Taiwan_Semiconductor") (part "FR207G"))
    )
    (comp (ref "VD20")
      (value "FR207G")
      (footprint "PcbLib_Discrete:DO-15")
      (description "Diode 2A, 1000V Glass Passivated Fast Recovery Rectifiers")
      (fields (field (name "MANUFACTURER") "Taiwan Semiconductor Corporation"))
      (libsource (lib "Schlib_Taiwan_Semiconductor") (part "FR207G"))
    )
    (comp (ref "VD21")
      (value "FR207G")
      (footprint "PcbLib_Discrete:DO-15")
      (description "Diode 2A, 1000V Glass Passivated Fast Recovery Rectifiers")
      (fields (field (name "MANUFACTURER") "Taiwan Semiconductor Corporation"))
      (libsource (lib "Schlib_Taiwan_Semiconductor") (part "FR207G"))
    )
    (comp (ref "VD22")
      (value "STPS3045CW")
      (footprint "PcbLib_ICs:TO-247_with_TO-220 (VERTICAL)")
      (description "Power Schottky Rectifier Diode 45V, 2x15A")
      (fields (field (name "MANUFACTURER") "STMicroelectronics"))
      (libsource (lib "Schlib_STMicroelectronics") (part "STPS3045CW"))
    )
    (comp (ref "VD23")
      (value "STPS3045CW")
      (footprint "PcbLib_ICs:TO-247_with_TO-220 (VERTICAL)")
      (description "Power Schottky Rectifier Diode 45V, 2x15A")
      (fields (field (name "MANUFACTURER") "STMicroelectronics"))
      (libsource (lib "Schlib_STMicroelectronics") (part "STPS3045CW"))
    )
    (comp (ref "VT4")
      (value "FCH20N60")
      (footprint "PcbLib_ICs:TO-247_with_TO-220 (VERTICAL)")
      (description "600V @ 20A N-Channel MOSFET")
      (fields (field (name "MANUFACTURER") "ON Semiconductor"))
      (libsource (lib "Schlib_ONSemiconductor") (part "FCH20N60"))
    )
    (comp (ref "VT5")
      (value "FCH20N60")
      (footprint "PcbLib_ICs:TO-247_with_TO-220 (VERTICAL)")
      (description "600V @ 20A N-Channel MOSFET")
      (fields (field (name "MANUFACTURER") "ON Semiconductor"))
      (libsource (lib "Schlib_ONSemiconductor") (part "FCH20N60"))
    )
    (comp (ref "VT6")
      (value "2SA733")
      (footprint "PcbLib_ICs:TO-92 (VERTICAL,LINE)")
      (description "General Purpose p-n-p Transistors")
      (fields (field (name "MANUFACTURER") "NEC"))
      (libsource (lib "Schlib_NEC") (part "2SA733"))
    )
    (comp (ref "VT7")
      (value "FQA70N15")
      (footprint "PcbLib_ICs:TO-3PN_with_TO-220 (VERTICAL)")
      (description "150V @ 70A 28 mΩ N-Channel MOSFET")
      (fields (field (name "MANUFACTURER") "ON Semiconductor"))
      (libsource (lib "Schlib_ONSemiconductor") (part "FQA70N15"))
    )
    (comp (ref "VT8")
      (value "FQA70N15")
      (footprint "PcbLib_ICs:TO-3PN_with_TO-220 (VERTICAL)")
      (description "150V @ 70A 28 mΩ N-Channel MOSFET")
      (fields (field (name "MANUFACTURER") "ON Semiconductor"))
      (libsource (lib "Schlib_ONSemiconductor") (part "FQA70N15"))
    )
    (comp (ref "VT9")
      (value "2SC945")
      (footprint "PcbLib_ICs:TO-92 (VERTICAL,LINE)")
      (description "General Purpose n-p-n Transistors")
      (fields (field (name "MANUFACTURER") "NEC"))
      (libsource (lib "Schlib_NEC") (part "2SC945"))
    )
    (comp (ref "VT10")
      (value "2SA733")
      (footprint "PcbLib_ICs:TO-92 (VERTICAL,LINE)")
      (description "General Purpose p-n-p Transistors")
      (fields (field (name "MANUFACTURER") "NEC"))
      (libsource (lib "Schlib_NEC") (part "2SA733"))
    )
    (comp (ref "XS3")
      (value "DG340-3.81-02P-12")
      (footprint "PcbLib_Connectors:DG340-3.81-02P")
      (description "2-way screw terminal, pitch 150mils (3.81mm)")
      (fields (field (name "MANUFACTURER") "DEGSON"))
      (libsource (lib "Schlib_OtherComponents") (part "DG340-3.81-02P-12"))
    )
    (comp (ref "XS4")
      (value "DG340-3.81-02P-12")
      (footprint "PcbLib_Connectors:DG340-3.81-02P")
      (description "2-way screw terminal, pitch 150mils (3.81mm)")
      (fields (field (name "MANUFACTURER") "DEGSON"))
      (libsource (lib "Schlib_OtherComponents") (part "DG340-3.81-02P-12"))
    )
    (comp (ref "XS5")
      (value "DG340-3.81-02P-12")
      (footprint "PcbLib_Connectors:DG340-3.81-02P")
      (description "2-way screw terminal, pitch 150mils (3.81mm)")
      (fields (field (name "MANUFACTURER") "DEGSON"))
      (libsource (lib "Schlib_OtherComponents") (part "DG340-3.81-02P-12"))
    )
    (comp (ref "XS6")
      (value "DG500-5.08-02P-14")
      (footprint "PcbLib_Connectors:DG500-5.08-02P")
      (description "2-way screw terminal, pitch 200mils (5.08mm)")
      (fields (field (name "MANUFACTURER") "DEGSON"))
      (libsource (lib "Schlib_OtherComponents") (part "DG500-5.08-02P-14"))
    )
    (comp (ref "XS7")
      (value "DG500-5.08-02P-14")
      (footprint "PcbLib_Connectors:DG500-5.08-02P")
      (description "2-way screw terminal, pitch 200mils (5.08mm)")
      (fields (field (name "MANUFACTURER") "DEGSON"))
      (libsource (lib "Schlib_OtherComponents") (part "DG500-5.08-02P-14"))
    )
  )
  (nets
    (net (code "1") (name "/0V") (class "Default")
      (node (ref "C46") (pin "1") (pinfunction "1_1") (pintype "passive"))
      (node (ref "C49") (pin "1") (pinfunction "1_1") (pintype "passive"))
      (node (ref "C50") (pin "1") (pinfunction "1_1") (pintype "passive"))
      (node (ref "C51") (pin "2") (pinfunction "2_2") (pintype "passive"))
      (node (ref "C52") (pin "2") (pinfunction "2_2") (pintype "passive"))
      (node (ref "C53") (pin "2") (pinfunction "2_2") (pintype "passive"))
      (node (ref "C55") (pin "2") (pinfunction "2_2") (pintype "passive"))
      (node (ref "C56") (pin "1") (pinfunction "1_1") (pintype "passive"))
      (node (ref "KT20") (pin "1") (pinfunction "1_1") (pintype "passive"))
      (node (ref "KT23") (pin "1") (pinfunction "1_1") (pintype "passive"))
      (node (ref "R63") (pin "2") (pinfunction "2_2") (pintype "passive"))
      (node (ref "R65") (pin "2") (pinfunction "2_2") (pintype "passive"))
      (node (ref "R66") (pin "1") (pinfunction "1_1") (pintype "passive"))
      (node (ref "R67") (pin "2") (pinfunction "2_2") (pintype "passive"))
      (node (ref "VD22") (pin "1") (pinfunction "A1_1") (pintype "passive"))
      (node (ref "VD22") (pin "3") (pinfunction "A2_3") (pintype "passive"))
      (node (ref "VD23") (pin "1") (pinfunction "A1_1") (pintype "passive"))
      (node (ref "VD23") (pin "3") (pinfunction "A2_3") (pintype "passive"))
      (node (ref "VT7") (pin "3") (pinfunction "S_3") (pintype "passive"))
      (node (ref "VT8") (pin "3") (pinfunction "S_3") (pintype "passive"))
      (node (ref "XS7") (pin "1") (pinfunction "1_1") (pintype "passive"))
      (node (ref "XS7") (pin "2") (pinfunction "2_2") (pintype "passive"))
    )
    (net (code "2") (name "/ALERT_ISO") (class "Default")
      (node (ref "DA10") (pin "4") (pinfunction "COLLECTOR_4") (pintype "passive"))
      (node (ref "R55") (pin "2") (pinfunction "2_2") (pintype "passive"))
      (node (ref "XS4") (pin "1") (pinfunction "1_1") (pintype "passive"))
    )
    (net (code "3") (name "/CLR_ALERT_ISO") (class "Default")
      (node (ref "R59") (pin "2") (pinfunction "2_2") (pintype "passive"))
      (node (ref "XS3") (pin "2") (pinfunction "2_2") (pintype "passive"))
    )
    (net (code "4") (name "/DAC_VSET") (class "Default")
      (node (ref "DA80") (pin "3") (pinfunction "IN+_3") (pintype "input"))
      (node (ref "XS5") (pin "1") (pinfunction "1_1") (pintype "passive"))
    )
    (net (code "5") (name "/HALF_OFF_ISO") (class "Default")
      (node (ref "R57") (pin "2") (pinfunction "2_2") (pintype "passive"))
      (node (ref "XS3") (pin "1") (pinfunction "1_1") (pintype "passive"))
    )
    (net (code "6") (name "/HALF_VS") (class "Default")
      (node (ref "C41") (pin "1") (pinfunction "1_1") (pintype "passive"))
      (node (ref "KT3") (pin "1") (pinfunction "1_1") (pintype "passive"))
      (node (ref "R37") (pin "1") (pinfunction "1_1") (pintype "passive"))
      (node (ref "R41") (pin "1") (pinfunction "1_1") (pintype "passive"))
      (node (ref "T2") (pin "5") (pinfunction "5_5") (pintype "passive"))
      (node (ref "VD19") (pin "2") (pinfunction "A_2") (pintype "passive"))
      (node (ref "VD21") (pin "2") (pinfunction "A_2") (pintype "passive"))
      (node (ref "VT4") (pin "3") (pinfunction "S_3") (pintype "passive"))
      (node (ref "VT5") (pin "2") (pinfunction "D_2") (pintype "passive"))
    )
    (net (code "7") (name "/VOUT") (class "Default")
      (node (ref "C46") (pin "2") (pinfunction "2_2") (pintype "passive"))
      (node (ref "C49") (pin "2") (pinfunction "2_2") (pintype "passive"))
      (node (ref "C50") (pin "2") (pinfunction "2_2") (pintype "passive"))
      (node (ref "C51") (pin "1") (pinfunction "1_1") (pintype "passive"))
      (node (ref "C52") (pin "1") (pinfunction "1_1") (pintype "passive"))
      (node (ref "C53") (pin "1") (pinfunction "1_1") (pintype "passive"))
      (node (ref "C55") (pin "1") (pinfunction "1_1") (pintype "passive"))
      (node (ref "C56") (pin "2") (pinfunction "2_2") (pintype "passive"))
      (node (ref "L10") (pin "2") (pinfunction "2_2") (pintype "passive"))
      (node (ref "R66") (pin "2") (pinfunction "2_2") (pintype "passive"))
      (node (ref "XS6") (pin "1") (pinfunction "1_1") (pintype "passive"))
      (node (ref "XS6") (pin "2") (pinfunction "2_2") (pintype "passive"))
    )
    (net (code "8") (name "CLR_ALERT") (class "Default")
      (node (ref "DA9") (pin "4") (pinfunction "COLLECTOR_4") (pintype "passive"))
      (node (ref "KT10") (pin "1") (pinfunction "1_1") (pintype "passive"))
      (node (ref "R49") (pin "2") (pinfunction "2_2") (pintype "passive"))
    )
    (net (code "9") (name "FB_CURRENT") (class "Default")
      (node (ref "KT6") (pin "1") (pinfunction "1_1") (pintype "passive"))
    )
    (net (code "10") (name "FB_VOLTAGE") (class "Default")
      (node (ref "DA7") (pin "6") (pinfunction "COLLECTOR2_6") (pintype "passive"))
      (node (ref "KT7") (pin "1") (pinfunction "1_1") (pintype "passive"))
      (node (ref "R47") (pin "1") (pinfunction "1_1") (pintype "passive"))
    )
    (net (code "11") (name "GND") (class "Default")
      (node (ref "C47") (pin "2") (pinfunction "2_2") (pintype "passive"))
      (node (ref "C48") (pin "2") (pinfunction "2_2") (pintype "passive"))
      (node (ref "DA10") (pin "3") (pinfunction "EMITTER_3") (pintype "passive"))
      (node (ref "DA6") (pin "2") (pinfunction "CATHODE_2") (pintype "power_in"))
      (node (ref "DA7") (pin "4") (pinfunction "CATHODE2_4") (pintype "power_in"))
      (node (ref "DA7") (pin "7") (pinfunction "EMITTER1_7") (pintype "passive"))
      (node (ref "DA80") (pin "4") (pinfunction "V-_4") (pintype "power_in"))
      (node (ref "KT25") (pin "1") (pinfunction "1_1") (pintype "passive"))
      (node (ref "R51") (pin "1") (pinfunction "1_1") (pintype "passive"))
      (node (ref "R54") (pin "2") (pinfunction "2_2") (pintype "passive"))
      (node (ref "R56") (pin "2") (pinfunction "2_2") (pintype "passive"))
      (node (ref "R64") (pin "2") (pinfunction "2_2") (pintype "passive"))
      (node (ref "R65") (pin "1") (pinfunction "1_1") (pintype "passive"))
      (node (ref "R67") (pin "1") (pinfunction "1_1") (pintype "passive"))
      (node (ref "VT9") (pin "3") (pinfunction "E_3") (pintype "passive"))
      (node (ref "XS4") (pin "2") (pinfunction "2_2") (pintype "passive"))
      (node (ref "XS5") (pin "2") (pinfunction "2_2") (pintype "passive"))
    )
    (net (code "12") (name "HALF_BRIDGE_OFF") (class "Default")
      (node (ref "DA8") (pin "4") (pinfunction "COLLECTOR_4") (pintype "passive"))
      (node (ref "KT17") (pin "1") (pinfunction "1_1") (pintype "passive"))
      (node (ref "R48") (pin "2") (pinfunction "2_2") (pintype "passive"))
    )
    (net (code "13") (name "HALF_SD#") (class "Default")
      (node (ref "KT8") (pin "1") (pinfunction "1_1") (pintype "passive"))
    )
    (net (code "14") (name "Net-(C43-Pad2)") (class "Default")
      (node (ref "C43") (pin "2") (pinfunction "2_2") (pintype "passive"))
      (node (ref "C44") (pin "1") (pinfunction "1_1") (pintype "passive"))
      (node (ref "R73") (pin "1") (pinfunction "1_1") (pintype "passive"))
      (node (ref "R74") (pin "2") (pinfunction "2_2") (pintype "passive"))
      (node (ref "T2") (pin "1") (pinfunction "1_1") (pintype "passive"))
    )
    (net (code "15") (name "Net-(C45-Pad2)") (class "Default")
      (node (ref "C45") (pin "2") (pinfunction "2_2") (pintype "passive"))
      (node (ref "T2") (pin "6") (pinfunction "6_6") (pintype "passive"))
    )
    (net (code "16") (name "Net-(DA5A-1IN+)") (class "Default")
      (node (ref "C40") (pin "1") (pinfunction "1_1") (pintype "passive"))
      (node (ref "DA5") (pin "3") (pinfunction "1IN+_3") (pintype "input"))
      (node (ref "R42") (pin "2") (pinfunction "2_2") (pintype "passive"))
      (node (ref "VD14") (pin "2") (pinfunction "2_2") (pintype "passive"))
      (node (ref "VD15") (pin "1") (pinfunction "1_1") (pintype "passive"))
    )
    (net (code "17") (name "Net-(DA5A-1IN-)") (class "Default")
      (node (ref "C40") (pin "2") (pinfunction "2_2") (pintype "passive"))
      (node (ref "DA5") (pin "2") (pinfunction "1IN-_2") (pintype "input"))
      (node (ref "R36") (pin "1") (pinfunction "1_1") (pintype "passive"))
      (node (ref "R43") (pin "2") (pinfunction "2_2") (pintype "passive"))
      (node (ref "VD16") (pin "2") (pinfunction "2_2") (pintype "passive"))
      (node (ref "VD17") (pin "1") (pinfunction "1_1") (pintype "passive"))
    )
    (net (code "18") (name "Net-(DA5A-1OUT)") (class "Default")
      (node (ref "DA5") (pin "1") (pinfunction "1OUT_1") (pintype "output"))
      (node (ref "DA5") (pin "5") (pinfunction "2IN+_5") (pintype "input"))
      (node (ref "R36") (pin "2") (pinfunction "2_2") (pintype "passive"))
    )
    (net (code "19") (name "Net-(DA5A-V+)") (class "Default")
      (node (ref "C38") (pin "1") (pinfunction "1_1") (pintype "passive"))
      (node (ref "C39") (pin "1") (pinfunction "1_1") (pintype "passive"))
      (node (ref "DA5") (pin "8") (pinfunction "V+_8") (pintype "power_in"))
      (node (ref "L9") (pin "1") (pinfunction "1_1") (pintype "passive"))
    )
    (net (code "20") (name "Net-(DA6-ANODE)") (class "Default")
      (node (ref "DA6") (pin "1") (pinfunction "ANODE_1") (pintype "passive"))
      (node (ref "R53") (pin "1") (pinfunction "1_1") (pintype "passive"))
      (node (ref "R54") (pin "1") (pinfunction "1_1") (pintype "passive"))
    )
    (net (code "21") (name "Net-(DA7A-ANODE1)") (class "Default")
      (node (ref "DA7") (pin "1") (pinfunction "ANODE1_1") (pintype "passive"))
      (node (ref "R60") (pin "1") (pinfunction "1_1") (pintype "passive"))
    )
    (net (code "22") (name "Net-(DA7A-CATHODE1)") (class "Default")
      (node (ref "DA7") (pin "2") (pinfunction "CATHODE1_2") (pintype "power_in"))
      (node (ref "DA7") (pin "3") (pinfunction "ANODE2_3") (pintype "passive"))
    )
    (net (code "23") (name "Net-(DA7A-COLLECTOR1)") (class "Default")
      (node (ref "DA7") (pin "8") (pinfunction "COLLECTOR1_8") (pintype "passive"))
      (node (ref "DA80") (pin "2") (pinfunction "IN-_2") (pintype "input"))
      (node (ref "R61") (pin "2") (pinfunction "2_2") (pintype "passive"))
    )
    (net (code "24") (name "Net-(DA8-ANODE)") (class "Default")
      (node (ref "DA8") (pin "1") (pinfunction "ANODE_1") (pintype "passive"))
      (node (ref "R52") (pin "2") (pinfunction "2_2") (pintype "passive"))
    )
    (net (code "25") (name "Net-(DA8-CATHODE)") (class "Default")
      (node (ref "DA8") (pin "2") (pinfunction "CATHODE_2") (pintype "power_in"))
      (node (ref "VT9") (pin "2") (pinfunction "C_2") (pintype "passive"))
    )
    (net (code "26") (name "Net-(DA9-ANODE)") (class "Default")
      (node (ref "DA9") (pin "1") (pinfunction "ANODE_1") (pintype "passive"))
      (node (ref "VT10") (pin "2") (pinfunction "C_2") (pintype "passive"))
    )
    (net (code "27") (name "Net-(DA9-CATHODE)") (class "Default")
      (node (ref "DA9") (pin "2") (pinfunction "CATHODE_2") (pintype "power_in"))
      (node (ref "R51") (pin "2") (pinfunction "2_2") (pintype "passive"))
    )
    (net (code "28") (name "Net-(DA10-ANODE)") (class "Default")
      (node (ref "DA10") (pin "1") (pinfunction "ANODE_1") (pintype "passive"))
      (node (ref "VT6") (pin "2") (pinfunction "C_2") (pintype "passive"))
    )
    (net (code "29") (name "Net-(DA10-CATHODE)") (class "Default")
      (node (ref "DA10") (pin "2") (pinfunction "CATHODE_2") (pintype "power_in"))
      (node (ref "R50") (pin "2") (pinfunction "2_2") (pintype "passive"))
    )
    (net (code "30") (name "Net-(DA11B-2IN+)") (class "Default")
      (node (ref "C54") (pin "1") (pinfunction "1_1") (pintype "passive"))
      (node (ref "DA11") (pin "5") (pinfunction "2IN+_5") (pintype "input"))
      (node (ref "R63") (pin "1") (pinfunction "1_1") (pintype "passive"))
    )
    (net (code "31") (name "Net-(DA11B-2IN-)") (class "Default")
      (node (ref "C54") (pin "2") (pinfunction "2_2") (pintype "passive"))
      (node (ref "DA11") (pin "6") (pinfunction "2IN-_6") (pintype "input"))
      (node (ref "R62") (pin "1") (pinfunction "1_1") (pintype "passive"))
      (node (ref "R64") (pin "1") (pinfunction "1_1") (pintype "passive"))
    )
    (net (code "32") (name "Net-(DA11B-2OUT)") (class "Default")
      (node (ref "DA11") (pin "7") (pinfunction "2OUT_7") (pintype "output"))
      (node (ref "R53") (pin "2") (pinfunction "2_2") (pintype "passive"))
      (node (ref "R62") (pin "2") (pinfunction "2_2") (pintype "passive"))
    )
    (net (code "33") (name "Net-(DA80-OUT)") (class "Default")
      (node (ref "DA80") (pin "6") (pinfunction "OUT_6") (pintype "output"))
      (node (ref "R60") (pin "2") (pinfunction "2_2") (pintype "passive"))
    )
    (net (code "34") (name "Net-(DA80-V+)") (class "Default")
      (node (ref "C47") (pin "1") (pinfunction "1_1") (pintype "passive"))
      (node (ref "C48") (pin "1") (pinfunction "1_1") (pintype "passive"))
      (node (ref "DA80") (pin "7") (pinfunction "V+_7") (pintype "power_in"))
      (node (ref "L11") (pin "1") (pinfunction "1_1") (pintype "passive"))
      (node (ref "R61") (pin "1") (pinfunction "1_1") (pintype "passive"))
    )
    (net (code "35") (name "Net-(L10-Pad1)") (class "Default")
      (node (ref "L10") (pin "1") (pinfunction "1_1") (pintype "passive"))
      (node (ref "T2") (pin "11") (pinfunction "11_11") (pintype "passive"))
      (node (ref "T2") (pin "12") (pinfunction "12_12") (pintype "passive"))
    )
    (net (code "36") (name "Net-(VD12-A)") (class "Default")
      (node (ref "R34") (pin "1") (pinfunction "1_1") (pintype "passive"))
      (node (ref "R37") (pin "2") (pinfunction "2_2") (pintype "passive"))
      (node (ref "VD12") (pin "2") (pinfunction "A_2") (pintype "passive"))
      (node (ref "VT4") (pin "1") (pinfunction "G_1") (pintype "passive"))
    )
    (net (code "37") (name "Net-(VD13-A)") (class "Default")
      (node (ref "R35") (pin "1") (pinfunction "1_1") (pintype "passive"))
      (node (ref "R38") (pin "2") (pinfunction "2_2") (pintype "passive"))
      (node (ref "VD13") (pin "2") (pinfunction "A_2") (pintype "passive"))
      (node (ref "VT5") (pin "1") (pinfunction "G_1") (pintype "passive"))
    )
    (net (code "38") (name "Net-(VD18-C)") (class "Default")
      (node (ref "C41") (pin "2") (pinfunction "2_2") (pintype "passive"))
      (node (ref "R40") (pin "1") (pinfunction "1_1") (pintype "passive"))
      (node (ref "VD18") (pin "1") (pinfunction "C_1") (pintype "passive"))
      (node (ref "VD20") (pin "1") (pinfunction "C_1") (pintype "passive"))
    )
    (net (code "39") (name "Net-(VD19-C)") (class "Default")
      (node (ref "C42") (pin "2") (pinfunction "2_2") (pintype "passive"))
      (node (ref "R41") (pin "2") (pinfunction "2_2") (pintype "passive"))
      (node (ref "VD19") (pin "1") (pinfunction "C_1") (pintype "passive"))
      (node (ref "VD21") (pin "1") (pinfunction "C_1") (pintype "passive"))
    )
    (net (code "40") (name "Net-(VD22-C)") (class "Default")
      (node (ref "KT18") (pin "1") (pinfunction "1_1") (pintype "passive"))
      (node (ref "T2") (pin "13") (pinfunction "13_13") (pintype "passive"))
      (node (ref "T2") (pin "14") (pinfunction "14_14") (pintype "passive"))
      (node (ref "VD22") (pin "2") (pinfunction "C_2") (pintype "passive"))
      (node (ref "VT7") (pin "2") (pinfunction "D_2") (pintype "passive"))
    )
    (net (code "41") (name "Net-(VD23-C)") (class "Default")
      (node (ref "KT21") (pin "1") (pinfunction "1_1") (pintype "passive"))
      (node (ref "T2") (pin "10") (pinfunction "10_10") (pintype "passive"))
      (node (ref "T2") (pin "9") (pinfunction "9_9") (pintype "passive"))
      (node (ref "VD23") (pin "2") (pinfunction "C_2") (pintype "passive"))
      (node (ref "VT8") (pin "2") (pinfunction "D_2") (pintype "passive"))
    )
    (net (code "42") (name "Net-(VT5-S)") (class "Default")
      (node (ref "R39") (pin "2") (pinfunction "2_2") (pintype "passive"))
      (node (ref "R42") (pin "1") (pinfunction "1_1") (pintype "passive"))
      (node (ref "VT5") (pin "3") (pinfunction "S_3") (pintype "passive"))
    )
    (net (code "43") (name "Net-(VT6-B)") (class "Default")
      (node (ref "R44") (pin "2") (pinfunction "2_2") (pintype "passive"))
      (node (ref "R45") (pin "1") (pinfunction "1_1") (pintype "passive"))
      (node (ref "VT6") (pin "1") (pinfunction "B_1") (pintype "passive"))
    )
    (net (code "44") (name "Net-(VT7-G)") (class "Default")
      (node (ref "KT19") (pin "1") (pinfunction "1_1") (pintype "passive"))
      (node (ref "VT7") (pin "1") (pinfunction "G_1") (pintype "passive"))
    )
    (net (code "45") (name "Net-(VT8-G)") (class "Default")
      (node (ref "KT22") (pin "1") (pinfunction "1_1") (pintype "passive"))
      (node (ref "VT8") (pin "1") (pinfunction "G_1") (pintype "passive"))
    )
    (net (code "46") (name "Net-(VT9-B)") (class "Default")
      (node (ref "R56") (pin "1") (pinfunction "1_1") (pintype "passive"))
      (node (ref "R57") (pin "1") (pinfunction "1_1") (pintype "passive"))
      (node (ref "VT9") (pin "1") (pinfunction "B_1") (pintype "passive"))
    )
    (net (code "47") (name "Net-(VT10-B)") (class "Default")
      (node (ref "R58") (pin "1") (pinfunction "1_1") (pintype "passive"))
      (node (ref "R59") (pin "1") (pinfunction "1_1") (pintype "passive"))
      (node (ref "VT10") (pin "1") (pinfunction "B_1") (pintype "passive"))
    )
    (net (code "48") (name "OVER_CURRENT_HALF_BRIDGE") (class "Default")
      (node (ref "DA5") (pin "6") (pinfunction "2IN-_6") (pintype "input"))
      (node (ref "DA5") (pin "7") (pinfunction "2OUT_7") (pintype "output"))
      (node (ref "KT13") (pin "1") (pinfunction "1_1") (pintype "passive"))
    )
    (net (code "49") (name "OVER_CURRENT_RECTIFIER") (class "Default")
      (node (ref "DA6") (pin "4") (pinfunction "COLLECTOR_4") (pintype "passive"))
      (node (ref "KT14") (pin "1") (pinfunction "1_1") (pintype "passive"))
      (node (ref "R46") (pin "2") (pinfunction "2_2") (pintype "passive"))
    )
    (net (code "50") (name "OVER_TEMP_HALF_BRIDGE") (class "Default")
      (node (ref "KT15") (pin "1") (pinfunction "1_1") (pintype "passive"))
    )
    (net (code "51") (name "OVER_TEMP_RECTIFIER") (class "Default")
      (node (ref "KT16") (pin "1") (pinfunction "1_1") (pintype "passive"))
    )
    (net (code "52") (name "PGND") (class "Default")
      (node (ref "C38") (pin "2") (pinfunction "2_2") (pintype "passive"))
      (node (ref "C39") (pin "2") (pinfunction "2_2") (pintype "passive"))
      (node (ref "C42") (pin "1") (pinfunction "1_1") (pintype "passive"))
      (node (ref "C44") (pin "2") (pinfunction "2_2") (pintype "passive"))
      (node (ref "C45") (pin "1") (pinfunction "1_1") (pintype "passive"))
      (node (ref "DA5") (pin "4") (pinfunction "V-_4") (pintype "power_in"))
      (node (ref "DA6") (pin "3") (pinfunction "EMITTER_3") (pintype "passive"))
      (node (ref "DA7") (pin "5") (pinfunction "EMITTER2_5") (pintype "passive"))
      (node (ref "DA8") (pin "3") (pinfunction "EMITTER_3") (pintype "passive"))
      (node (ref "DA9") (pin "3") (pinfunction "EMITTER_3") (pintype "passive"))
      (node (ref "KT12") (pin "1") (pinfunction "1_1") (pintype "passive"))
      (node (ref "KT5") (pin "1") (pinfunction "1_1") (pintype "passive"))
      (node (ref "R38") (pin "1") (pinfunction "1_1") (pintype "passive"))
      (node (ref "R39") (pin "1") (pinfunction "1_1") (pintype "passive"))
      (node (ref "R43") (pin "1") (pinfunction "1_1") (pintype "passive"))
      (node (ref "R50") (pin "1") (pinfunction "1_1") (pintype "passive"))
      (node (ref "R74") (pin "1") (pinfunction "1_1") (pintype "passive"))
      (node (ref "VD15") (pin "2") (pinfunction "2_2") (pintype "passive"))
      (node (ref "VD17") (pin "2") (pinfunction "2_2") (pintype "passive"))
    )
    (net (code "53") (name "PWM_ALERT") (class "Default")
      (node (ref "KT9") (pin "1") (pinfunction "1_1") (pintype "passive"))
      (node (ref "R44") (pin "1") (pinfunction "1_1") (pintype "passive"))
    )
    (net (code "54") (name "PWM_H") (class "Default")
      (node (ref "KT4") (pin "1") (pinfunction "1_1") (pintype "passive"))
      (node (ref "R34") (pin "2") (pinfunction "2_2") (pintype "passive"))
      (node (ref "VD12") (pin "1") (pinfunction "C_1") (pintype "passive"))
    )
    (net (code "55") (name "PWM_L") (class "Default")
      (node (ref "KT2") (pin "1") (pinfunction "1_1") (pintype "passive"))
      (node (ref "R35") (pin "2") (pinfunction "2_2") (pintype "passive"))
      (node (ref "VD13") (pin "1") (pinfunction "C_1") (pintype "passive"))
    )
    (net (code "56") (name "VCC_380V") (class "Default")
      (node (ref "C43") (pin "1") (pinfunction "1_1") (pintype "passive"))
      (node (ref "R40") (pin "2") (pinfunction "2_2") (pintype "passive"))
      (node (ref "R73") (pin "2") (pinfunction "2_2") (pintype "passive"))
      (node (ref "VD18") (pin "2") (pinfunction "A_2") (pintype "passive"))
      (node (ref "VD20") (pin "2") (pinfunction "A_2") (pintype "passive"))
      (node (ref "VT4") (pin "2") (pinfunction "D_2") (pintype "passive"))
    )
    (net (code "57") (name "VCC_NONISO_12V0P") (class "Default")
      (node (ref "KT1") (pin "1") (pinfunction "1_1") (pintype "passive"))
      (node (ref "L9") (pin "2") (pinfunction "2_2") (pintype "passive"))
      (node (ref "R45") (pin "2") (pinfunction "2_2") (pintype "passive"))
      (node (ref "R46") (pin "1") (pinfunction "1_1") (pintype "passive"))
      (node (ref "R47") (pin "2") (pinfunction "2_2") (pintype "passive"))
      (node (ref "R48") (pin "1") (pinfunction "1_1") (pintype "passive"))
      (node (ref "R49") (pin "1") (pinfunction "1_1") (pintype "passive"))
      (node (ref "VD14") (pin "1") (pinfunction "1_1") (pintype "passive"))
      (node (ref "VD16") (pin "1") (pinfunction "1_1") (pintype "passive"))
      (node (ref "VT6") (pin "3") (pinfunction "E_3") (pintype "passive"))
    )
    (net (code "58") (name "VCC_STANDBY_12V0P") (class "Default")
      (node (ref "KT24") (pin "1") (pinfunction "1_1") (pintype "passive"))
      (node (ref "L11") (pin "2") (pinfunction "2_2") (pintype "passive"))
      (node (ref "R52") (pin "1") (pinfunction "1_1") (pintype "passive"))
      (node (ref "R55") (pin "1") (pinfunction "1_1") (pintype "passive"))
      (node (ref "R58") (pin "2") (pinfunction "2_2") (pintype "passive"))
      (node (ref "VT10") (pin "3") (pinfunction "E_3") (pintype "passive"))
    )
    (net (code "59") (name "unconnected-(DA40-IN+-Pad3)") (class "Default")
      (node (ref "DA40") (pin "3") (pinfunction "IN+_3") (pintype "input"))
    )
    (net (code "60") (name "unconnected-(DA40-IN--Pad2)") (class "Default")
      (node (ref "DA40") (pin "2") (pinfunction "IN-_2") (pintype "input"))
    )
    (net (code "61") (name "unconnected-(DA40-OUT-Pad6)") (class "Default")
      (node (ref "DA40") (pin "6") (pinfunction "OUT_6") (pintype "output"))
    )
    (net (code "62") (name "unconnected-(DA40-RG1-Pad1)") (class "Default")
      (node (ref "DA40") (pin "1") (pinfunction "RG1_1") (pintype "passive"))
    )
    (net (code "63") (name "unconnected-(DA40-RG2-Pad8)") (class "Default")
      (node (ref "DA40") (pin "8") (pinfunction "RG2_8") (pintype "passive"))
    )
    (net (code "64") (name "unconnected-(DA40-Ref-Pad5)") (class "Default")
      (node (ref "DA40") (pin "5") (pinfunction "Ref_5") (pintype "passive"))
    )
    (net (code "65") (name "unconnected-(DA40-V+-Pad7)") (class "Default")
      (node (ref "DA40") (pin "7") (pinfunction "V+_7") (pintype "power_in"))
    )
    (net (code "66") (name "unconnected-(DA40-V--Pad4)") (class "Default")
      (node (ref "DA40") (pin "4") (pinfunction "V-_4") (pintype "power_in"))
    )
    (net (code "67") (name "unconnected-(DA50-IN+-Pad3)") (class "Default")
      (node (ref "DA50") (pin "3") (pinfunction "IN+_3") (pintype "input"))
    )
    (net (code "68") (name "unconnected-(DA50-IN--Pad2)") (class "Default")
      (node (ref "DA50") (pin "2") (pinfunction "IN-_2") (pintype "input"))
    )
    (net (code "69") (name "unconnected-(DA50-OUT-Pad6)") (class "Default")
      (node (ref "DA50") (pin "6") (pinfunction "OUT_6") (pintype "output"))
    )
    (net (code "70") (name "unconnected-(DA50-RG1-Pad1)") (class "Default")
      (node (ref "DA50") (pin "1") (pinfunction "RG1_1") (pintype "passive"))
    )
    (net (code "71") (name "unconnected-(DA50-RG2-Pad8)") (class "Default")
      (node (ref "DA50") (pin "8") (pinfunction "RG2_8") (pintype "passive"))
    )
    (net (code "72") (name "unconnected-(DA50-Ref-Pad5)") (class "Default")
      (node (ref "DA50") (pin "5") (pinfunction "Ref_5") (pintype "passive"))
    )
    (net (code "73") (name "unconnected-(DA50-V+-Pad7)") (class "Default")
      (node (ref "DA50") (pin "7") (pinfunction "V+_7") (pintype "power_in"))
    )
    (net (code "74") (name "unconnected-(DA50-V--Pad4)") (class "Default")
      (node (ref "DA50") (pin "4") (pinfunction "V-_4") (pintype "power_in"))
    )
    (net (code "75") (name "unconnected-(DA80-NC-Pad1)") (class "Default")
      (node (ref "DA80") (pin "1") (pinfunction "NC_1") (pintype "tri_state+no_connect"))
    )
    (net (code "76") (name "unconnected-(DA80-NC-Pad5)") (class "Default")
      (node (ref "DA80") (pin "5") (pinfunction "NC_5") (pintype "tri_state+no_connect"))
    )
    (net (code "77") (name "unconnected-(DA80-NC-Pad8)") (class "Default")
      (node (ref "DA80") (pin "8") (pinfunction "NC_8") (pintype "tri_state+no_connect"))
    )
    (net (code "78") (name "unconnected-(KT11-Pad1)") (class "Default")
      (node (ref "KT11") (pin "1") (pinfunction "1_1") (pintype "passive+no_connect"))
    )
    (net (code "79") (name "unconnected-(T2-Pad3)") (class "Default")
      (node (ref "T2") (pin "3") (pinfunction "3_3") (pintype "passive+no_connect"))
    )
  )
)
